# BMS028B_Monitor.net
KiCad netlist of a schematic drawn in Altium Designer
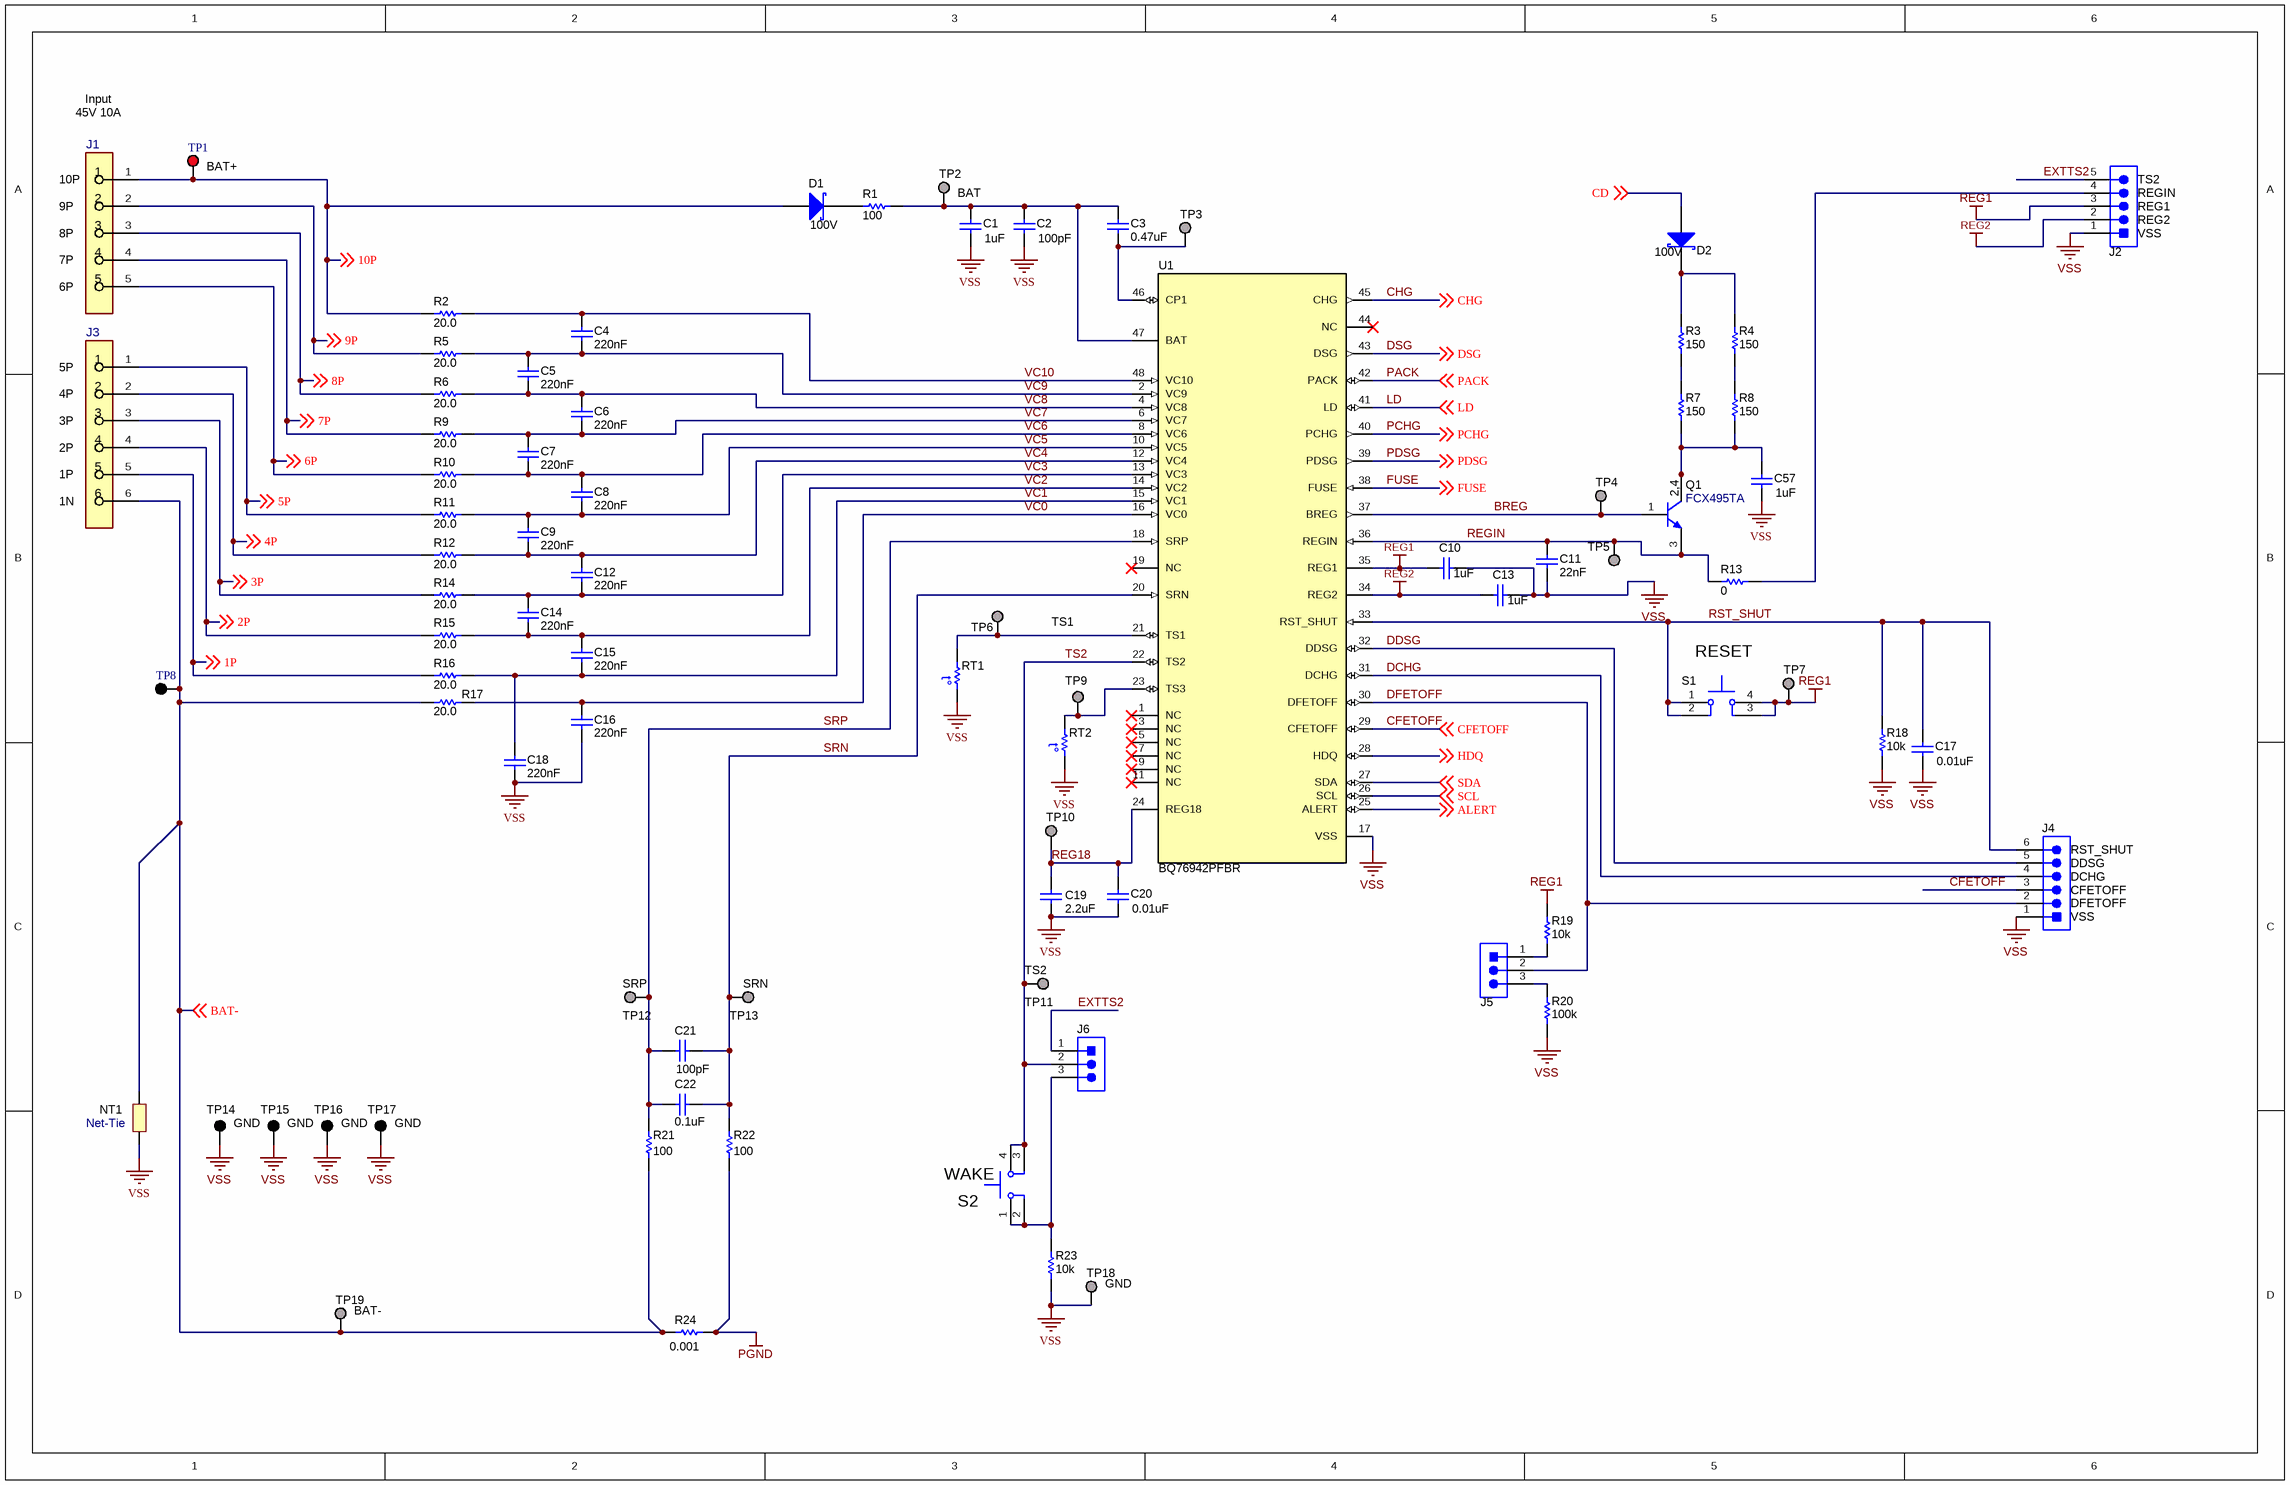
[diagram p0: BMS028B_Monitor.SchDoc]

(export (version "E")
  (design (tool "Eeschema 10.0.6"))
  (components
    (comp (ref "C1")
      (value "C3216X7R2A105K160AA")
      (footprint "1206_180")
      (description "CAP, CERM, 1 uF, 100 V, +/- 10%, X7R, 1206")
      (fields
        (field (name "MANUFACTURER") "TDK")
        (field (name "VALUEDISPLAYED") "1uF")
        (field (name "PUBLISHER") "Texas Instruments")
      )
      (libsource (lib "Altium Vault - TI") (part "Capacitor"))
    )
    (comp (ref "C2")
      (value "GCM1885C2A101JA16D")
      (footprint "0603")
      (description "CAP, CERM, 100 pF, 100 V, +/- 5%, C0G/NP0, AEC-Q200 Grade 1, 0603")
      (fields
        (field (name "MANUFACTURER") "MuRata")
        (field (name "VALUEDISPLAYED") "100pF")
        (field (name "PUBLISHER") "Texas Instruments")
      )
      (libsource (lib "Altium Vault - TI") (part "Capacitor"))
    )
    (comp (ref "C3")
      (value "GCM219R71E474KA55D")
      (footprint "0805_HV")
      (description "CAP, CERM, 0.47 uF, 25 V, +/- 10%, X7R, AEC-Q200 Grade 1, 0805")
      (fields
        (field (name "MANUFACTURER") "MuRata")
        (field (name "VALUEDISPLAYED") "0.47uF")
        (field (name "PUBLISHER") "Texas Instruments")
      )
      (libsource (lib "Altium Vault - TI") (part "Capacitor"))
    )
    (comp (ref "C4")
      (value "C1608X7R1H224K080AB")
      (footprint "0603S")
      (description "CAP, CERM, 0.22 uF, 50 V, +/- 10%, X7R, 0603")
      (fields
        (field (name "MANUFACTURER") "TDK")
        (field (name "CAP_F") "220nF")
        (field (name "PUBLISHER") "Texas Instruments")
      )
      (libsource (lib "Altium Vault - TI") (part "Capacitor"))
    )
    (comp (ref "C5")
      (value "C1608X7R1H224K080AB")
      (footprint "0603S")
      (description "CAP, CERM, 0.22 uF, 50 V, +/- 10%, X7R, 0603")
      (fields
        (field (name "MANUFACTURER") "TDK")
        (field (name "CAP_F") "220nF")
        (field (name "PUBLISHER") "Texas Instruments")
      )
      (libsource (lib "Altium Vault - TI") (part "Capacitor"))
    )
    (comp (ref "C6")
      (value "C1608X7R1H224K080AB")
      (footprint "0603S")
      (description "CAP, CERM, 0.22 uF, 50 V, +/- 10%, X7R, 0603")
      (fields
        (field (name "MANUFACTURER") "TDK")
        (field (name "CAP_F") "220nF")
        (field (name "PUBLISHER") "Texas Instruments")
      )
      (libsource (lib "Altium Vault - TI") (part "Capacitor"))
    )
    (comp (ref "C7")
      (value "C1608X7R1H224K080AB")
      (footprint "0603S")
      (description "CAP, CERM, 0.22 uF, 50 V, +/- 10%, X7R, 0603")
      (fields
        (field (name "MANUFACTURER") "TDK")
        (field (name "CAP_F") "220nF")
        (field (name "PUBLISHER") "Texas Instruments")
      )
      (libsource (lib "Altium Vault - TI") (part "Capacitor"))
    )
    (comp (ref "C8")
      (value "C1608X7R1H224K080AB")
      (footprint "0603S")
      (description "CAP, CERM, 0.22 uF, 50 V, +/- 10%, X7R, 0603")
      (fields
        (field (name "MANUFACTURER") "TDK")
        (field (name "CAP_F") "220nF")
        (field (name "PUBLISHER") "Texas Instruments")
      )
      (libsource (lib "Altium Vault - TI") (part "Capacitor"))
    )
    (comp (ref "C9")
      (value "C1608X7R1H224K080AB")
      (footprint "0603S")
      (description "CAP, CERM, 0.22 uF, 50 V, +/- 10%, X7R, 0603")
      (fields
        (field (name "MANUFACTURER") "TDK")
        (field (name "CAP_F") "220nF")
        (field (name "PUBLISHER") "Texas Instruments")
      )
      (libsource (lib "Altium Vault - TI") (part "Capacitor"))
    )
    (comp (ref "C10")
      (value "EMK212B7105KG-T")
      (footprint "0805_HV")
      (description "CAP, CERM, 1 uF, 16 V, +/- 10%, X7R, 0805")
      (fields
        (field (name "MANUFACTURER") "Taiyo Yuden")
        (field (name "VALUEDISPLAYED") "1uF")
        (field (name "PUBLISHER") "Texas Instruments")
      )
      (libsource (lib "Altium Vault - TI") (part "Capacitor"))
    )
    (comp (ref "C11")
      (value "C0603C223K4RACTU")
      (footprint "0603")
      (description "CAP, CERM, 0.022 uF, 16 V, +/- 10%, X7R, 0603")
      (fields
        (field (name "MANUFACTURER") "Kemet")
        (field (name "CAP_F") "22nF")
        (field (name "PUBLISHER") "Texas Instruments")
      )
      (libsource (lib "Altium Vault - TI") (part "Capacitor"))
    )
    (comp (ref "C12")
      (value "C1608X7R1H224K080AB")
      (footprint "0603S")
      (description "CAP, CERM, 0.22 uF, 50 V, +/- 10%, X7R, 0603")
      (fields
        (field (name "MANUFACTURER") "TDK")
        (field (name "CAP_F") "220nF")
        (field (name "PUBLISHER") "Texas Instruments")
      )
      (libsource (lib "Altium Vault - TI") (part "Capacitor"))
    )
    (comp (ref "C13")
      (value "EMK212B7105KG-T")
      (footprint "0805_HV")
      (description "CAP, CERM, 1 uF, 16 V, +/- 10%, X7R, 0805")
      (fields
        (field (name "MANUFACTURER") "Taiyo Yuden")
        (field (name "VALUEDISPLAYED") "1uF")
        (field (name "PUBLISHER") "Texas Instruments")
      )
      (libsource (lib "Altium Vault - TI") (part "Capacitor"))
    )
    (comp (ref "C14")
      (value "C1608X7R1H224K080AB")
      (footprint "0603S")
      (description "CAP, CERM, 0.22 uF, 50 V, +/- 10%, X7R, 0603")
      (fields
        (field (name "MANUFACTURER") "TDK")
        (field (name "CAP_F") "220nF")
        (field (name "PUBLISHER") "Texas Instruments")
      )
      (libsource (lib "Altium Vault - TI") (part "Capacitor"))
    )
    (comp (ref "C15")
      (value "C1608X7R1H224K080AB")
      (footprint "0603S")
      (description "CAP, CERM, 0.22 uF, 50 V, +/- 10%, X7R, 0603")
      (fields
        (field (name "MANUFACTURER") "TDK")
        (field (name "CAP_F") "220nF")
        (field (name "PUBLISHER") "Texas Instruments")
      )
      (libsource (lib "Altium Vault - TI") (part "Capacitor"))
    )
    (comp (ref "C16")
      (value "C1608X7R1H224K080AB")
      (footprint "0603S")
      (description "CAP, CERM, 0.22 uF, 50 V, +/- 10%, X7R, 0603")
      (fields
        (field (name "MANUFACTURER") "TDK")
        (field (name "CAP_F") "220nF")
        (field (name "PUBLISHER") "Texas Instruments")
      )
      (libsource (lib "Altium Vault - TI") (part "Capacitor"))
    )
    (comp (ref "C17")
      (value "885012206040")
      (footprint "0603")
      (description "CAP, CERM, 0.01 uF, 16 V, +/- 10%, X7R, 0603")
      (fields
        (field (name "MANUFACTURER") "Wurth Elektronik")
        (field (name "VALUEDISPLAYED") "0.01uF")
        (field (name "PUBLISHER") "Texas Instruments")
      )
      (libsource (lib "Altium Vault - TI") (part "Capacitor"))
    )
    (comp (ref "C18")
      (value "C1608X7R1H224K080AB")
      (footprint "0603S")
      (description "CAP, CERM, 0.22 uF, 50 V, +/- 10%, X7R, 0603")
      (fields
        (field (name "MANUFACTURER") "TDK")
        (field (name "CAP_F") "220nF")
        (field (name "PUBLISHER") "Texas Instruments")
      )
      (libsource (lib "Altium Vault - TI") (part "Capacitor"))
    )
    (comp (ref "C19")
      (value "EMK212B7225KG-T")
      (footprint "0805_HV")
      (description "CAP, CERM, 2.2 uF, 16 V, +/- 10%, X7R, 0805")
      (fields
        (field (name "MANUFACTURER") "Taiyo Yuden")
        (field (name "VALUEDISPLAYED") "2.2uF")
        (field (name "PUBLISHER") "Texas Instruments")
      )
      (libsource (lib "Altium Vault - TI") (part "Capacitor"))
    )
    (comp (ref "C20")
      (value "885012206040")
      (footprint "0603")
      (description "CAP, CERM, 0.01 uF, 16 V, +/- 10%, X7R, 0603")
      (fields
        (field (name "MANUFACTURER") "Wurth Elektronik")
        (field (name "VALUEDISPLAYED") "0.01uF")
        (field (name "PUBLISHER") "Texas Instruments")
      )
      (libsource (lib "Altium Vault - TI") (part "Capacitor"))
    )
    (comp (ref "C21")
      (value "C0603C101J5GACTU")
      (footprint "0603")
      (description "CAP, CERM, 100 pF, 50 V, +/- 5%, C0G/NP0, 0603")
      (fields
        (field (name "MANUFACTURER") "Kemet")
        (field (name "VALUEDISPLAYED") "100pF")
        (field (name "PUBLISHER") "Texas Instruments")
      )
      (libsource (lib "Altium Vault - TI") (part "Capacitor"))
    )
    (comp (ref "C22")
      (value "885012206095")
      (footprint "0603")
      (description "CAP, CERM, 0.1 uF, 50 V, +/- 10%, X7R, 0603")
      (fields
        (field (name "MANUFACTURER") "Wurth Elektronik")
        (field (name "VALUEDISPLAYED") "0.1uF")
        (field (name "PUBLISHER") "Texas Instruments")
      )
      (libsource (lib "Altium Vault - TI") (part "Capacitor"))
    )
    (comp (ref "C57")
      (value "C3216X7R2A105K160AA")
      (footprint "1206_180")
      (description "CAP, CERM, 1 uF, 100 V, +/- 10%, X7R, 1206")
      (fields
        (field (name "MANUFACTURER") "TDK")
        (field (name "VALUEDISPLAYED") "1uF")
        (field (name "PUBLISHER") "Texas Instruments")
      )
      (libsource (lib "Altium Vault - TI") (part "Capacitor"))
    )
    (comp (ref "D1")
      (value "100V")
      (footprint "SOD-123")
      (description "Diode, Schottky, 100 V, 0.15 A, SOD-123")
      (fields (field (name "MANUFACTURER") "Diodes Inc.") (field (name "PARTNUMBER") "BAT46W-7-F"))
      (libsource (lib "Altium Vault - TI") (part "DIODE_SCHOTTKY"))
    )
    (comp (ref "D2")
      (value "100V")
      (footprint "SOD-123")
      (description "Diode, Schottky, 100 V, 0.15 A, SOD-123")
      (fields (field (name "MANUFACTURER") "Diodes Inc.") (field (name "PARTNUMBER") "BAT46W-7-F"))
      (libsource (lib "Altium Vault - TI") (part "DIODE_SCHOTTKY"))
    )
    (comp (ref "J1")
      (value "OSTTE050161")
      (footprint "FP-OSTTE050161_HDR5-MFG")
      (description "TERM BLOCK 3.5MM VERT 5POS PCB")
      (fields (field (name "MANUFACTURER") "On Shore Technology"))
      (libsource (lib "Altium Vault - TI") (part "SYM-OSTTE050161"))
    )
    (comp (ref "J2")
      (value "PEC05SAAN")
      (footprint "Sullins_PxC05SAAN")
      (description "Header, 2.54mm, 5x1, Tin, TH")
      (fields
        (field (name "MANUFACTURER") "Sullins Connector Solutions")
        (field (name "PUBLISHER") "Texas Instruments")
      )
      (libsource (lib "Altium Vault - TI") (part "CMP-0054597-1"))
    )
    (comp (ref "J3")
      (value "OSTTE060161")
      (footprint "FP-OSTTE060161_HDR6-MFG")
      (description "TERM BLOCK 3.5MM VERT 6POS PCB")
      (fields (field (name "MANUFACTURER") "On Shore Technology"))
      (libsource (lib "Altium Vault - TI") (part "SYM-OSTTE060161"))
    )
    (comp (ref "J4")
      (value "PEC06SAAN")
      (footprint "Sullins_PEC06SAAN")
      (description "Header, 100mil, 6x1, Tin, TH")
      (fields
        (field (name "MANUFACTURER") "Sullins Connector Solutions")
        (field (name "PUBLISHER") "Texas Instruments")
      )
      (libsource (lib "Altium Vault - TI") (part "Header_6x1"))
    )
    (comp (ref "J5")
      (value "87898-0304")
      (footprint "Molex_87898-0304")
      (description "Header, 2.54mm, 3x1, Gold, SMT")
      (fields (field (name "MANUFACTURER") "Molex") (field (name "PUBLISHER") "Texas Instruments"))
      (libsource (lib "") (part "CMP-0075388-1_1"))
    )
    (comp (ref "J6")
      (value "87898-0304")
      (footprint "Molex_87898-0304")
      (description "Header, 2.54mm, 3x1, Gold, SMT")
      (fields (field (name "MANUFACTURER") "Molex") (field (name "PUBLISHER") "Texas Instruments"))
      (libsource (lib "Altium Vault - TI") (part "CMP-0075388-1"))
    )
    (comp (ref "NT1")
      (value "Net-Tie")
      (footprint "Net-Tie_10milWide_30milLong")
      (description "Single point connection between nets.")
      (libsource (lib "Altium Vault - TI") (part "Net-Tie"))
    )
    (comp (ref "Q1")
      (value "FCX495TA")
      (footprint "SOT-89-3")
      (description "Transistor, NPN, 150 V, 1 A, AEC-Q101, SOT-89")
      (fields (field (name "MANUFACTURER") "Diodes Inc.") (field (name "PUBLISHER") "Texas Instruments"))
      (libsource (lib "Altium Vault - TI") (part "BJT_NPN_C24B1E3"))
    )
    (comp (ref "R1")
      (value "Resistor")
      (footprint "0603")
      (description "RES, 100, 5%, 0.1 W, AEC-Q200 Grade 0, 0603")
      (fields
        (field (name "PARTNUMBER") "CRCW0603100RJNEA")
        (field (name "MANUFACTURER") "Vishay-Dale")
        (field (name "VALUEDISPLAYED") "100")
        (field (name "PUBLISHER") "Texas Instruments")
      )
      (libsource (lib "Altium Vault - TI") (part "Resistor"))
    )
    (comp (ref "R2")
      (value "CRCW120620R0FKEA")
      (footprint "1206")
      (description "RES, 20.0, 1%, 0.25 W, AEC-Q200 Grade 0, 1206")
      (fields (field (name "MANUFACTURER") "Vishay-Dale") (field (name "VALUEDISPLAYED") "20.0"))
      (libsource (lib "Altium Vault - TI") (part "Resistor"))
    )
    (comp (ref "R3")
      (value "CRCW2512150RJNEG")
      (footprint "2512")
      (description "RES, 150, 5%, 1 W, AEC-Q200 Grade 0, 2512")
      (fields (field (name "MANUFACTURER") "Vishay-Dale") (field (name "VALUEDISPLAYED") "150"))
      (libsource (lib "Altium Vault - TI") (part "Resistor"))
    )
    (comp (ref "R4")
      (value "CRCW2512150RJNEG")
      (footprint "2512")
      (description "RES, 150, 5%, 1 W, AEC-Q200 Grade 0, 2512")
      (fields (field (name "MANUFACTURER") "Vishay-Dale") (field (name "VALUEDISPLAYED") "150"))
      (libsource (lib "Altium Vault - TI") (part "Resistor"))
    )
    (comp (ref "R5")
      (value "CRCW120620R0FKEA")
      (footprint "1206")
      (description "RES, 20.0, 1%, 0.25 W, AEC-Q200 Grade 0, 1206")
      (fields (field (name "MANUFACTURER") "Vishay-Dale") (field (name "VALUEDISPLAYED") "20.0"))
      (libsource (lib "Altium Vault - TI") (part "Resistor"))
    )
    (comp (ref "R6")
      (value "CRCW120620R0FKEA")
      (footprint "1206")
      (description "RES, 20.0, 1%, 0.25 W, AEC-Q200 Grade 0, 1206")
      (fields (field (name "MANUFACTURER") "Vishay-Dale") (field (name "VALUEDISPLAYED") "20.0"))
      (libsource (lib "Altium Vault - TI") (part "CMP-0016781-3"))
    )
    (comp (ref "R7")
      (value "CRCW2512150RJNEG")
      (footprint "2512")
      (description "RES, 150, 5%, 1 W, AEC-Q200 Grade 0, 2512")
      (fields (field (name "MANUFACTURER") "Vishay-Dale") (field (name "VALUEDISPLAYED") "150"))
      (libsource (lib "Altium Vault - TI") (part "Resistor"))
    )
    (comp (ref "R8")
      (value "CRCW2512150RJNEG")
      (footprint "2512")
      (description "RES, 150, 5%, 1 W, AEC-Q200 Grade 0, 2512")
      (fields (field (name "MANUFACTURER") "Vishay-Dale") (field (name "VALUEDISPLAYED") "150"))
      (libsource (lib "Altium Vault - TI") (part "Resistor"))
    )
    (comp (ref "R9")
      (value "CRCW120620R0FKEA")
      (footprint "1206")
      (description "RES, 20.0, 1%, 0.25 W, AEC-Q200 Grade 0, 1206")
      (fields (field (name "MANUFACTURER") "Vishay-Dale") (field (name "VALUEDISPLAYED") "20.0"))
      (libsource (lib "Altium Vault - TI") (part "Resistor"))
    )
    (comp (ref "R10")
      (value "CRCW120620R0FKEA")
      (footprint "1206")
      (description "RES, 20.0, 1%, 0.25 W, AEC-Q200 Grade 0, 1206")
      (fields (field (name "MANUFACTURER") "Vishay-Dale") (field (name "VALUEDISPLAYED") "20.0"))
      (libsource (lib "Altium Vault - TI") (part "Resistor"))
    )
    (comp (ref "R11")
      (value "CRCW120620R0FKEA")
      (footprint "1206")
      (description "RES, 20.0, 1%, 0.25 W, AEC-Q200 Grade 0, 1206")
      (fields (field (name "MANUFACTURER") "Vishay-Dale") (field (name "VALUEDISPLAYED") "20.0"))
      (libsource (lib "Altium Vault - TI") (part "Resistor"))
    )
    (comp (ref "R12")
      (value "CRCW120620R0FKEA")
      (footprint "1206")
      (description "RES, 20.0, 1%, 0.25 W, AEC-Q200 Grade 0, 1206")
      (fields (field (name "MANUFACTURER") "Vishay-Dale") (field (name "VALUEDISPLAYED") "20.0"))
      (libsource (lib "Altium Vault - TI") (part "Resistor"))
    )
    (comp (ref "R13")
      (value "CRCW06030000Z0EA")
      (footprint "0603")
      (description "RES, 0, 5%, 0.1 W, AEC-Q200 Grade 0, 0603")
      (fields (field (name "MANUFACTURER") "Vishay-Dale") (field (name "VALUEDISPLAYED") "0"))
      (libsource (lib "Altium Vault - TI") (part "Resistor"))
    )
    (comp (ref "R14")
      (value "CRCW120620R0FKEA")
      (footprint "1206")
      (description "RES, 20.0, 1%, 0.25 W, AEC-Q200 Grade 0, 1206")
      (fields (field (name "MANUFACTURER") "Vishay-Dale") (field (name "VALUEDISPLAYED") "20.0"))
      (libsource (lib "Altium Vault - TI") (part "Resistor"))
    )
    (comp (ref "R15")
      (value "CRCW120620R0FKEA")
      (footprint "1206")
      (description "RES, 20.0, 1%, 0.25 W, AEC-Q200 Grade 0, 1206")
      (fields (field (name "MANUFACTURER") "Vishay-Dale") (field (name "VALUEDISPLAYED") "20.0"))
      (libsource (lib "Altium Vault - TI") (part "Resistor"))
    )
    (comp (ref "R16")
      (value "CRCW120620R0FKEA")
      (footprint "1206")
      (description "RES, 20.0, 1%, 0.25 W, AEC-Q200 Grade 0, 1206")
      (fields (field (name "MANUFACTURER") "Vishay-Dale") (field (name "VALUEDISPLAYED") "20.0"))
      (libsource (lib "Altium Vault - TI") (part "Resistor"))
    )
    (comp (ref "R17")
      (value "CRCW120620R0FKEA")
      (footprint "1206")
      (description "RES, 20.0, 1%, 0.25 W, AEC-Q200 Grade 0, 1206")
      (fields (field (name "MANUFACTURER") "Vishay-Dale") (field (name "VALUEDISPLAYED") "20.0"))
      (libsource (lib "Altium Vault - TI") (part "Resistor"))
    )
    (comp (ref "R18")
      (value "CRCW060310K0JNEA")
      (footprint "0603")
      (description "RES, 10 k, 5%, 0.1 W, AEC-Q200 Grade 0, 0603")
      (fields (field (name "MANUFACTURER") "Vishay-Dale") (field (name "VALUEDISPLAYED") "10k"))
      (libsource (lib "Altium Vault - TI") (part "Resistor"))
    )
    (comp (ref "R19")
      (value "CRCW060310K0JNEA")
      (footprint "0603")
      (description "RES, 10 k, 5%, 0.1 W, AEC-Q200 Grade 0, 0603")
      (fields (field (name "MANUFACTURER") "Vishay-Dale") (field (name "VALUEDISPLAYED") "10k"))
      (libsource (lib "Altium Vault - TI") (part "Resistor"))
    )
    (comp (ref "R20")
      (value "CRCW0603100KJNEA")
      (footprint "0603")
      (description "RES, 100 k, 5%, 0.1 W, AEC-Q200 Grade 0, 0603")
      (fields (field (name "MANUFACTURER") "Vishay-Dale") (field (name "VALUEDISPLAYED") "100k"))
      (libsource (lib "Altium Vault - TI") (part "Resistor"))
    )
    (comp (ref "R21")
      (value "Resistor")
      (footprint "0603")
      (description "RES, 100, 5%, 0.1 W, AEC-Q200 Grade 0, 0603")
      (fields
        (field (name "PARTNUMBER") "CRCW0603100RJNEA")
        (field (name "MANUFACTURER") "Vishay-Dale")
        (field (name "VALUEDISPLAYED") "100")
        (field (name "PUBLISHER") "Texas Instruments")
      )
      (libsource (lib "Altium Vault - TI") (part "Resistor"))
    )
    (comp (ref "R22")
      (value "Resistor")
      (footprint "0603")
      (description "RES, 100, 5%, 0.1 W, AEC-Q200 Grade 0, 0603")
      (fields
        (field (name "PARTNUMBER") "CRCW0603100RJNEA")
        (field (name "MANUFACTURER") "Vishay-Dale")
        (field (name "VALUEDISPLAYED") "100")
        (field (name "PUBLISHER") "Texas Instruments")
      )
      (libsource (lib "Altium Vault - TI") (part "Resistor"))
    )
    (comp (ref "R23")
      (value "CRCW060310K0JNEA")
      (footprint "0603")
      (description "RES, 10 k, 5%, 0.1 W, AEC-Q200 Grade 0, 0603")
      (fields (field (name "MANUFACTURER") "Vishay-Dale") (field (name "VALUEDISPLAYED") "10k"))
      (libsource (lib "Altium Vault - TI") (part "Resistor"))
    )
    (comp (ref "R24")
      (value "Resistor")
      (footprint "1210M")
      (description "RES, 0.001, 1%, 1 W, 1210")
      (fields
        (field (name "PARTNUMBER") "PMR25HZPFV1L00")
        (field (name "MANUFACTURER") "Rohm")
        (field (name "VALUEDISPLAYED") "0.001")
        (field (name "PUBLISHER") "Texas Instruments")
      )
      (libsource (lib "Altium Vault - TI") (part "Resistor"))
    )
    (comp (ref "RT1")
      (value "Thermistor")
      (footprint "THERMISTOR_103AT-2")
      (description "Thermistor NTC, 10.0k ohm, 1%, Disc, 5x8.4 mm")
      (fields
        (field (name "PARTNUMBER") "103AT-2")
        (field (name "MANUFACTURER") "SEMITEC Corporation")
        (field (name "PUBLISHER") "Texas Instruments")
      )
      (libsource (lib "Altium Vault - TI") (part "Thermistor"))
    )
    (comp (ref "RT2")
      (value "Thermistor")
      (footprint "THERMISTOR_103AT-2")
      (description "Thermistor NTC, 10.0k ohm, 1%, Disc, 5x8.4 mm")
      (fields
        (field (name "PARTNUMBER") "103AT-2")
        (field (name "MANUFACTURER") "SEMITEC Corporation")
        (field (name "PUBLISHER") "Texas Instruments")
      )
      (libsource (lib "Altium Vault - TI") (part "Thermistor"))
    )
    (comp (ref "S1")
      (value "SW_KST221JLFS")
      (footprint "SW_KST221JLFS")
      (description "Switch, Tactile, SPST-NO, SMT")
      (fields
        (field (name "PARTNUMBER") "KST221JLFS")
        (field (name "MANUFACTURER") "C&K Components")
        (field (name "SYMBOLCREATOR") "a0799628")
        (field (name "PUBLISHER") "Texas Instruments")
      )
      (libsource (lib "Altium Vault - TI") (part "SW_KST221JLFS"))
    )
    (comp (ref "S2")
      (value "SW_KST221JLFS")
      (footprint "SW_KST221JLFS")
      (description "Switch, Tactile, SPST-NO, SMT")
      (fields
        (field (name "PARTNUMBER") "KST221JLFS")
        (field (name "MANUFACTURER") "C&K Components")
        (field (name "SYMBOLCREATOR") "a0799628")
        (field (name "PUBLISHER") "Texas Instruments")
      )
      (libsource (lib "Altium Vault - TI") (part "SW_KST221JLFS"))
    )
    (comp (ref "TP1")
      (value "TESTPOINT")
      (footprint "Keystone5010")
      (description "Test Point, Multipurpose, Red, TH")
      (fields
        (field (name "MANUFACTURER") "Keystone")
        (field (name "PARTNUMBER") "5010")
        (field (name "PUBLISHER") "Texas Instruments")
      )
      (libsource (lib "Altium Vault - TI") (part "5010"))
    )
    (comp (ref "TP2")
      (value "TESTPOINT")
      (footprint "TP_VIA_060RND040")
      (description "TEST POINT.  No entry in BOM.")
      (libsource (lib "Altium Vault - TI") (part "TESTPOINT"))
    )
    (comp (ref "TP3")
      (value "TESTPOINT")
      (footprint "TP_VIA_060RND040")
      (description "TEST POINT.  No entry in BOM.")
      (libsource (lib "Altium Vault - TI") (part "CMP-0078143-2"))
    )
    (comp (ref "TP4")
      (value "TESTPOINT")
      (footprint "TP_VIA_060RND040")
      (description "TEST POINT.  No entry in BOM.")
      (libsource (lib "Altium Vault - TI") (part "CMP-0078143-2"))
    )
    (comp (ref "TP5")
      (value "TESTPOINT")
      (footprint "TP_VIA_060RND040")
      (description "TEST POINT.  No entry in BOM.")
      (libsource (lib "Altium Vault - TI") (part "CMP-0078143-2"))
    )
    (comp (ref "TP6")
      (value "TESTPOINT")
      (footprint "TP_VIA_060RND040")
      (description "TEST POINT.  No entry in BOM.")
      (libsource (lib "Altium Vault - TI") (part "CMP-0078143-2"))
    )
    (comp (ref "TP7")
      (value "TESTPOINT")
      (footprint "TP_VIA_060RND040")
      (description "TEST POINT.  No entry in BOM.")
      (libsource (lib "Altium Vault - TI") (part "CMP-0078143-2"))
    )
    (comp (ref "TP8")
      (value "TESTPOINT")
      (footprint "Keystone5011")
      (description "Test Point, Multipurpose, Black, TH")
      (fields
        (field (name "MANUFACTURER") "Keystone")
        (field (name "PARTNUMBER") "5011")
        (field (name "PUBLISHER") "Texas Instruments")
      )
      (libsource (lib "Altium Vault - TI") (part "5011"))
    )
    (comp (ref "TP9")
      (value "TESTPOINT")
      (footprint "TP_VIA_060RND040")
      (description "TEST POINT.  No entry in BOM.")
      (libsource (lib "Altium Vault - TI") (part "CMP-0078143-2"))
    )
    (comp (ref "TP10")
      (value "TESTPOINT")
      (footprint "TP_50MIL-25MILHOLE")
      (description "TEST POINT.  No entry in BOM.")
      (libsource (lib "Altium Vault - TI") (part "CMP-0078143-2"))
    )
    (comp (ref "TP11")
      (value "TESTPOINT")
      (footprint "TP_50MIL-25MILHOLE")
      (description "TEST POINT.  No entry in BOM.")
      (libsource (lib "Altium Vault - TI") (part "CMP-0078143-2"))
    )
    (comp (ref "TP12")
      (value "TESTPOINT")
      (footprint "TP_50MIL-25MILHOLE")
      (description "TEST POINT.  No entry in BOM.")
      (libsource (lib "Altium Vault - TI") (part "CMP-0078143-2"))
    )
    (comp (ref "TP13")
      (value "TESTPOINT")
      (footprint "TP_50MIL-25MILHOLE")
      (description "TEST POINT.  No entry in BOM.")
      (libsource (lib "Altium Vault - TI") (part "CMP-0078143-2"))
    )
    (comp (ref "TP14")
      (value "5006")
      (footprint "Keystone5006")
      (description "Test Point, Compact, Black, TH")
      (fields (field (name "MANUFACTURER") "Keystone") (field (name "PUBLISHER") "Texas Instruments"))
      (libsource (lib "Altium Vault - TI") (part "5006"))
    )
    (comp (ref "TP15")
      (value "5006")
      (footprint "Keystone5006")
      (description "Test Point, Compact, Black, TH")
      (fields (field (name "MANUFACTURER") "Keystone") (field (name "PUBLISHER") "Texas Instruments"))
      (libsource (lib "Altium Vault - TI") (part "5006"))
    )
    (comp (ref "TP16")
      (value "5006")
      (footprint "Keystone5006")
      (description "Test Point, Compact, Black, TH")
      (fields (field (name "MANUFACTURER") "Keystone") (field (name "PUBLISHER") "Texas Instruments"))
      (libsource (lib "Altium Vault - TI") (part "5006"))
    )
    (comp (ref "TP17")
      (value "5006")
      (footprint "Keystone5006")
      (description "Test Point, Compact, Black, TH")
      (fields (field (name "MANUFACTURER") "Keystone") (field (name "PUBLISHER") "Texas Instruments"))
      (libsource (lib "Altium Vault - TI") (part "5006"))
    )
    (comp (ref "TP18")
      (value "TESTPOINT")
      (footprint "TP_VIA_060RND040")
      (description "TEST POINT.  No entry in BOM.")
      (libsource (lib "Altium Vault - TI") (part "TESTPOINT"))
    )
    (comp (ref "TP19")
      (value "TESTPOINT")
      (footprint "TP_VIA_060RND040")
      (description "TEST POINT.  No entry in BOM.")
      (libsource (lib "Altium Vault - TI") (part "TESTPOINT"))
    )
    (comp (ref "U1")
      (value "BQ76942PFBR")
      (footprint "PFB0048A_N")
      (description "Multicell Battery Monitor and Protection Family, PFB0048A (TQFP-48)")
      (fields
        (field (name "ALTERNATE PARTNUMBER") "BQ76942PFBT")
        (field (name "MANUFACTURER") "Texas Instruments")
        (field (name "PARTNUMBER") "BQ76942PFBR")
      )
      (libsource (lib "Altium Vault - TI") (part "bq76942"))
    )
  )
  (nets
    (net (code "1") (name "/BREG") (class "Default")
      (node (ref "Q1") (pin "1") (pinfunction "B_1") (pintype "passive"))
      (node (ref "TP4") (pin "1") (pintype "passive"))
      (node (ref "U1") (pin "37") (pinfunction "BREG_37") (pintype "output"))
    )
    (net (code "2") (name "/DCHG") (class "Default")
      (node (ref "J4") (pin "4") (pinfunction "4_4") (pintype "passive"))
      (node (ref "U1") (pin "31") (pinfunction "DCHG_31") (pintype "bidirectional"))
    )
    (net (code "3") (name "/DDSG") (class "Default")
      (node (ref "J4") (pin "5") (pinfunction "5_5") (pintype "passive"))
      (node (ref "U1") (pin "32") (pinfunction "DDSG_32") (pintype "bidirectional"))
    )
    (net (code "4") (name "/DFETOFF") (class "Default")
      (node (ref "J4") (pin "2") (pinfunction "2_2") (pintype "passive"))
      (node (ref "J5") (pin "2") (pinfunction "2_2") (pintype "passive"))
      (node (ref "U1") (pin "30") (pinfunction "DFETOFF_30") (pintype "bidirectional"))
    )
    (net (code "5") (name "/EXTTS2") (class "Default")
      (node (ref "J2") (pin "5") (pinfunction "5_5") (pintype "passive"))
      (node (ref "J6") (pin "1") (pinfunction "1_1") (pintype "passive"))
    )
    (net (code "6") (name "/REG18") (class "Default")
      (node (ref "C19") (pin "2") (pinfunction "2_2") (pintype "passive"))
      (node (ref "C20") (pin "1") (pinfunction "1_1") (pintype "passive"))
      (node (ref "TP10") (pin "1") (pintype "passive"))
      (node (ref "U1") (pin "24") (pinfunction "REG18_24") (pintype "power_in"))
    )
    (net (code "7") (name "/REGIN") (class "Default")
      (node (ref "C11") (pin "2") (pinfunction "2_2") (pintype "passive"))
      (node (ref "Q1") (pin "3") (pinfunction "E_3") (pintype "passive"))
      (node (ref "R13") (pin "1") (pinfunction "1_1") (pintype "passive"))
      (node (ref "TP5") (pin "1") (pintype "passive"))
      (node (ref "U1") (pin "36") (pinfunction "REGIN_36") (pintype "input"))
    )
    (net (code "8") (name "/RST_SHUT") (class "Default")
      (node (ref "C17") (pin "1") (pinfunction "1_1") (pintype "passive"))
      (node (ref "J4") (pin "6") (pinfunction "6_6") (pintype "passive"))
      (node (ref "R18") (pin "1") (pinfunction "1_1") (pintype "passive"))
      (node (ref "S1") (pin "1") (pinfunction "1_1") (pintype "passive"))
      (node (ref "S1") (pin "2") (pinfunction "2_2") (pintype "passive"))
      (node (ref "U1") (pin "33") (pinfunction "RST_SHUT_33") (pintype "input"))
    )
    (net (code "9") (name "/SRN") (class "Default")
      (node (ref "C21") (pin "1") (pinfunction "1_1") (pintype "passive"))
      (node (ref "C22") (pin "2") (pinfunction "2_2") (pintype "passive"))
      (node (ref "R22") (pin "2") (pinfunction "2_2") (pintype "passive"))
      (node (ref "TP13") (pin "1") (pintype "passive"))
      (node (ref "U1") (pin "20") (pinfunction "SRN_20") (pintype "input"))
    )
    (net (code "10") (name "/SRP") (class "Default")
      (node (ref "C21") (pin "2") (pinfunction "2_2") (pintype "passive"))
      (node (ref "C22") (pin "1") (pinfunction "1_1") (pintype "passive"))
      (node (ref "R21") (pin "2") (pinfunction "2_2") (pintype "passive"))
      (node (ref "TP12") (pin "1") (pintype "passive"))
      (node (ref "U1") (pin "18") (pinfunction "SRP_18") (pintype "input"))
    )
    (net (code "11") (name "/TS2") (class "Default")
      (node (ref "J6") (pin "2") (pinfunction "2_2") (pintype "passive"))
      (node (ref "S2") (pin "3") (pinfunction "3_3") (pintype "passive"))
      (node (ref "S2") (pin "4") (pinfunction "4_4") (pintype "passive"))
      (node (ref "TP11") (pin "1") (pintype "passive"))
      (node (ref "U1") (pin "22") (pinfunction "TS2_22") (pintype "bidirectional"))
    )
    (net (code "12") (name "/VC0") (class "Default")
      (node (ref "C16") (pin "1") (pinfunction "1_1") (pintype "passive"))
      (node (ref "R17") (pin "2") (pinfunction "2_2") (pintype "passive"))
      (node (ref "U1") (pin "16") (pinfunction "VC0_16") (pintype "input"))
    )
    (net (code "13") (name "/VC1") (class "Default")
      (node (ref "C15") (pin "2") (pinfunction "2_2") (pintype "passive"))
      (node (ref "C18") (pin "1") (pinfunction "1_1") (pintype "passive"))
      (node (ref "R16") (pin "2") (pinfunction "2_2") (pintype "passive"))
      (node (ref "U1") (pin "15") (pinfunction "VC1_15") (pintype "input"))
    )
    (net (code "14") (name "/VC2") (class "Default")
      (node (ref "C14") (pin "2") (pinfunction "2_2") (pintype "passive"))
      (node (ref "C15") (pin "1") (pinfunction "1_1") (pintype "passive"))
      (node (ref "R15") (pin "2") (pinfunction "2_2") (pintype "passive"))
      (node (ref "U1") (pin "14") (pinfunction "VC2_14") (pintype "input"))
    )
    (net (code "15") (name "/VC3") (class "Default")
      (node (ref "C12") (pin "2") (pinfunction "2_2") (pintype "passive"))
      (node (ref "C14") (pin "1") (pinfunction "1_1") (pintype "passive"))
      (node (ref "R14") (pin "2") (pinfunction "2_2") (pintype "passive"))
      (node (ref "U1") (pin "13") (pinfunction "VC3_13") (pintype "input"))
    )
    (net (code "16") (name "/VC4") (class "Default")
      (node (ref "C12") (pin "1") (pinfunction "1_1") (pintype "passive"))
      (node (ref "C9") (pin "2") (pinfunction "2_2") (pintype "passive"))
      (node (ref "R12") (pin "2") (pinfunction "2_2") (pintype "passive"))
      (node (ref "U1") (pin "12") (pinfunction "VC4_12") (pintype "input"))
    )
    (net (code "17") (name "/VC5") (class "Default")
      (node (ref "C8") (pin "2") (pinfunction "2_2") (pintype "passive"))
      (node (ref "C9") (pin "1") (pinfunction "1_1") (pintype "passive"))
      (node (ref "R11") (pin "2") (pinfunction "2_2") (pintype "passive"))
      (node (ref "U1") (pin "10") (pinfunction "VC5_10") (pintype "input"))
    )
    (net (code "18") (name "/VC6") (class "Default")
      (node (ref "C7") (pin "2") (pinfunction "2_2") (pintype "passive"))
      (node (ref "C8") (pin "1") (pinfunction "1_1") (pintype "passive"))
      (node (ref "R10") (pin "2") (pinfunction "2_2") (pintype "passive"))
      (node (ref "U1") (pin "8") (pinfunction "VC6_8") (pintype "input"))
    )
    (net (code "19") (name "/VC7") (class "Default")
      (node (ref "C6") (pin "2") (pinfunction "2_2") (pintype "passive"))
      (node (ref "C7") (pin "1") (pinfunction "1_1") (pintype "passive"))
      (node (ref "R9") (pin "2") (pinfunction "2_2") (pintype "passive"))
      (node (ref "U1") (pin "6") (pinfunction "VC7_6") (pintype "input"))
    )
    (net (code "20") (name "/VC8") (class "Default")
      (node (ref "C5") (pin "2") (pinfunction "2_2") (pintype "passive"))
      (node (ref "C6") (pin "1") (pinfunction "1_1") (pintype "passive"))
      (node (ref "R6") (pin "2") (pinfunction "2_2") (pintype "passive"))
      (node (ref "U1") (pin "4") (pinfunction "VC8_4") (pintype "input"))
    )
    (net (code "21") (name "/VC9") (class "Default")
      (node (ref "C4") (pin "2") (pinfunction "2_2") (pintype "passive"))
      (node (ref "C5") (pin "1") (pinfunction "1_1") (pintype "passive"))
      (node (ref "R5") (pin "2") (pinfunction "2_2") (pintype "passive"))
      (node (ref "U1") (pin "2") (pinfunction "VC9_2") (pintype "input"))
    )
    (net (code "22") (name "/VC10") (class "Default")
      (node (ref "C4") (pin "1") (pinfunction "1_1") (pintype "passive"))
      (node (ref "R2") (pin "2") (pinfunction "2_2") (pintype "passive"))
      (node (ref "U1") (pin "48") (pinfunction "VC10_48") (pintype "input"))
    )
    (net (code "23") (name "1P") (class "Default")
      (node (ref "J3") (pin "5") (pinfunction "5_5") (pintype "passive"))
      (node (ref "R16") (pin "1") (pinfunction "1_1") (pintype "passive"))
    )
    (net (code "24") (name "2P") (class "Default")
      (node (ref "J3") (pin "4") (pinfunction "4_4") (pintype "passive"))
      (node (ref "R15") (pin "1") (pinfunction "1_1") (pintype "passive"))
    )
    (net (code "25") (name "3P") (class "Default")
      (node (ref "J3") (pin "3") (pinfunction "3_3") (pintype "passive"))
      (node (ref "R14") (pin "1") (pinfunction "1_1") (pintype "passive"))
    )
    (net (code "26") (name "4P") (class "Default")
      (node (ref "J3") (pin "2") (pinfunction "2_2") (pintype "passive"))
      (node (ref "R12") (pin "1") (pinfunction "1_1") (pintype "passive"))
    )
    (net (code "27") (name "5P") (class "Default")
      (node (ref "J3") (pin "1") (pinfunction "1_1") (pintype "passive"))
      (node (ref "R11") (pin "1") (pinfunction "1_1") (pintype "passive"))
    )
    (net (code "28") (name "6P") (class "Default")
      (node (ref "J1") (pin "5") (pinfunction "5_5") (pintype "passive"))
      (node (ref "R10") (pin "1") (pinfunction "1_1") (pintype "passive"))
    )
    (net (code "29") (name "7P") (class "Default")
      (node (ref "J1") (pin "4") (pinfunction "4_4") (pintype "passive"))
      (node (ref "R9") (pin "1") (pinfunction "1_1") (pintype "passive"))
    )
    (net (code "30") (name "8P") (class "Default")
      (node (ref "J1") (pin "3") (pinfunction "3_3") (pintype "passive"))
      (node (ref "R6") (pin "1") (pinfunction "1_1") (pintype "passive"))
    )
    (net (code "31") (name "9P") (class "Default")
      (node (ref "J1") (pin "2") (pinfunction "2_2") (pintype "passive"))
      (node (ref "R5") (pin "1") (pinfunction "1_1") (pintype "passive"))
    )
    (net (code "32") (name "10P") (class "Default")
      (node (ref "D1") (pin "2") (pinfunction "A_2") (pintype "passive"))
      (node (ref "J1") (pin "1") (pinfunction "1_1") (pintype "passive"))
      (node (ref "R2") (pin "1") (pinfunction "1_1") (pintype "passive"))
      (node (ref "TP1") (pin "1") (pintype "passive"))
    )
    (net (code "33") (name "ALERT") (class "Default")
      (node (ref "U1") (pin "25") (pinfunction "ALERT_25") (pintype "bidirectional"))
    )
    (net (code "34") (name "BAT-") (class "Default")
      (node (ref "J3") (pin "6") (pinfunction "6_6") (pintype "passive"))
      (node (ref "NT1") (pin "2") (pinfunction "2_2") (pintype "passive"))
      (node (ref "R17") (pin "1") (pinfunction "1_1") (pintype "passive"))
      (node (ref "R21") (pin "1") (pinfunction "1_1") (pintype "passive"))
      (node (ref "R24") (pin "2") (pinfunction "2_2") (pintype "passive"))
      (node (ref "TP19") (pin "1") (pintype "passive"))
      (node (ref "TP8") (pin "1") (pintype "passive"))
    )
    (net (code "35") (name "CD") (class "Default")
      (node (ref "D2") (pin "2") (pinfunction "A_2") (pintype "passive"))
    )
    (net (code "36") (name "CFETOFF") (class "Default")
      (node (ref "J4") (pin "3") (pinfunction "3_3") (pintype "passive"))
      (node (ref "U1") (pin "29") (pinfunction "CFETOFF_29") (pintype "bidirectional"))
    )
    (net (code "37") (name "CHG") (class "Default")
      (node (ref "U1") (pin "45") (pinfunction "CHG_45") (pintype "output"))
    )
    (net (code "38") (name "DSG") (class "Default")
      (node (ref "U1") (pin "43") (pinfunction "DSG_43") (pintype "output"))
    )
    (net (code "39") (name "FUSE") (class "Default")
      (node (ref "U1") (pin "38") (pinfunction "FUSE_38") (pintype "input"))
    )
    (net (code "40") (name "HDQ") (class "Default")
      (node (ref "U1") (pin "28") (pinfunction "HDQ_28") (pintype "bidirectional"))
    )
    (net (code "41") (name "LD") (class "Default")
      (node (ref "U1") (pin "41") (pinfunction "LD_41") (pintype "bidirectional"))
    )
    (net (code "42") (name "Net-(C57-Pad1)") (class "Default")
      (node (ref "C57") (pin "1") (pinfunction "1_1") (pintype "passive"))
      (node (ref "Q1") (pin "2") (pinfunction "C_2") (pintype "passive"))
      (node (ref "Q1") (pin "4") (pinfunction "C_4") (pintype "passive"))
      (node (ref "R7") (pin "1") (pinfunction "1_1") (pintype "passive"))
      (node (ref "R8") (pin "1") (pinfunction "1_1") (pintype "passive"))
    )
    (net (code "43") (name "Net-(D1-K)") (class "Default")
      (node (ref "D1") (pin "1") (pinfunction "K_1") (pintype "passive"))
      (node (ref "R1") (pin "2") (pinfunction "2_2") (pintype "passive"))
    )
    (net (code "44") (name "Net-(D2-K)") (class "Default")
      (node (ref "D2") (pin "1") (pinfunction "K_1") (pintype "passive"))
      (node (ref "R3") (pin "2") (pinfunction "2_2") (pintype "passive"))
      (node (ref "R4") (pin "2") (pinfunction "2_2") (pintype "passive"))
    )
    (net (code "45") (name "Net-(J2-Pad4)") (class "Default")
      (node (ref "J2") (pin "4") (pinfunction "4_4") (pintype "passive"))
      (node (ref "R13") (pin "2") (pinfunction "2_2") (pintype "passive"))
    )
    (net (code "46") (name "Net-(J5-Pad1)") (class "Default")
      (node (ref "J5") (pin "1") (pinfunction "1_1") (pintype "passive"))
      (node (ref "R19") (pin "2") (pinfunction "2_2") (pintype "passive"))
    )
    (net (code "47") (name "Net-(J5-Pad3)") (class "Default")
      (node (ref "J5") (pin "3") (pinfunction "3_3") (pintype "passive"))
      (node (ref "R20") (pin "2") (pinfunction "2_2") (pintype "passive"))
    )
    (net (code "48") (name "Net-(J6-Pad3)") (class "Default")
      (node (ref "J6") (pin "3") (pinfunction "3_3") (pintype "passive"))
      (node (ref "R23") (pin "2") (pinfunction "2_2") (pintype "passive"))
      (node (ref "S2") (pin "1") (pinfunction "1_1") (pintype "passive"))
      (node (ref "S2") (pin "2") (pinfunction "2_2") (pintype "passive"))
    )
    (net (code "49") (name "Net-(R3-Pad1)") (class "Default")
      (node (ref "R3") (pin "1") (pinfunction "1_1") (pintype "passive"))
      (node (ref "R7") (pin "2") (pinfunction "2_2") (pintype "passive"))
    )
    (net (code "50") (name "Net-(R4-Pad1)") (class "Default")
      (node (ref "R4") (pin "1") (pinfunction "1_1") (pintype "passive"))
      (node (ref "R8") (pin "2") (pinfunction "2_2") (pintype "passive"))
    )
    (net (code "51") (name "Net-(U1-BAT)") (class "Default")
      (node (ref "C1") (pin "1") (pinfunction "1_1") (pintype "passive"))
      (node (ref "C2") (pin "1") (pinfunction "1_1") (pintype "passive"))
      (node (ref "C3") (pin "1") (pinfunction "1_1") (pintype "passive"))
      (node (ref "R1") (pin "1") (pinfunction "1_1") (pintype "passive"))
      (node (ref "TP2") (pin "1") (pintype "passive"))
      (node (ref "U1") (pin "47") (pinfunction "BAT_47") (pintype "power_in"))
    )
    (net (code "52") (name "Net-(U1-CP1)") (class "Default")
      (node (ref "C3") (pin "2") (pinfunction "2_2") (pintype "passive"))
      (node (ref "TP3") (pin "1") (pintype "passive"))
      (node (ref "U1") (pin "46") (pinfunction "CP1_46") (pintype "bidirectional"))
    )
    (net (code "53") (name "Net-(U1-TS1)") (class "Default")
      (node (ref "RT1") (pin "1") (pinfunction "1_1") (pintype "passive"))
      (node (ref "TP6") (pin "1") (pintype "passive"))
      (node (ref "U1") (pin "21") (pinfunction "TS1_21") (pintype "bidirectional"))
    )
    (net (code "54") (name "Net-(U1-TS3)") (class "Default")
      (node (ref "RT2") (pin "1") (pinfunction "1_1") (pintype "passive"))
      (node (ref "TP9") (pin "1") (pintype "passive"))
      (node (ref "U1") (pin "23") (pinfunction "TS3_23") (pintype "bidirectional"))
    )
    (net (code "55") (name "PACK") (class "Default")
      (node (ref "U1") (pin "42") (pinfunction "PACK_42") (pintype "bidirectional"))
    )
    (net (code "56") (name "PCHG") (class "Default")
      (node (ref "U1") (pin "40") (pinfunction "PCHG_40") (pintype "output"))
    )
    (net (code "57") (name "PDSG") (class "Default")
      (node (ref "U1") (pin "39") (pinfunction "PDSG_39") (pintype "output"))
    )
    (net (code "58") (name "PGND") (class "Default")
      (node (ref "R22") (pin "1") (pinfunction "1_1") (pintype "passive"))
      (node (ref "R24") (pin "1") (pinfunction "1_1") (pintype "passive"))
    )
    (net (code "59") (name "REG1") (class "Default")
      (node (ref "C10") (pin "2") (pinfunction "2_2") (pintype "passive"))
      (node (ref "J2") (pin "3") (pinfunction "3_3") (pintype "passive"))
      (node (ref "R19") (pin "1") (pinfunction "1_1") (pintype "passive"))
      (node (ref "S1") (pin "3") (pinfunction "3_3") (pintype "passive"))
      (node (ref "S1") (pin "4") (pinfunction "4_4") (pintype "passive"))
      (node (ref "TP7") (pin "1") (pintype "passive"))
      (node (ref "U1") (pin "35") (pinfunction "REG1_35") (pintype "power_in"))
    )
    (net (code "60") (name "REG2") (class "Default")
      (node (ref "C13") (pin "2") (pinfunction "2_2") (pintype "passive"))
      (node (ref "J2") (pin "2") (pinfunction "2_2") (pintype "passive"))
      (node (ref "U1") (pin "34") (pinfunction "REG2_34") (pintype "power_in"))
    )
    (net (code "61") (name "SCL") (class "Default")
      (node (ref "U1") (pin "26") (pinfunction "SCL_26") (pintype "bidirectional"))
    )
    (net (code "62") (name "SDA") (class "Default")
      (node (ref "U1") (pin "27") (pinfunction "SDA_27") (pintype "bidirectional"))
    )
    (net (code "63") (name "VSS") (class "Default")
      (node (ref "C1") (pin "2") (pinfunction "2_2") (pintype "passive"))
      (node (ref "C10") (pin "1") (pinfunction "1_1") (pintype "passive"))
      (node (ref "C11") (pin "1") (pinfunction "1_1") (pintype "passive"))
      (node (ref "C13") (pin "1") (pinfunction "1_1") (pintype "passive"))
      (node (ref "C16") (pin "2") (pinfunction "2_2") (pintype "passive"))
      (node (ref "C17") (pin "2") (pinfunction "2_2") (pintype "passive"))
      (node (ref "C18") (pin "2") (pinfunction "2_2") (pintype "passive"))
      (node (ref "C19") (pin "1") (pinfunction "1_1") (pintype "passive"))
      (node (ref "C2") (pin "2") (pinfunction "2_2") (pintype "passive"))
      (node (ref "C20") (pin "2") (pinfunction "2_2") (pintype "passive"))
      (node (ref "C57") (pin "2") (pinfunction "2_2") (pintype "passive"))
      (node (ref "J2") (pin "1") (pinfunction "1_1") (pintype "passive"))
      (node (ref "J4") (pin "1") (pinfunction "1_1") (pintype "passive"))
      (node (ref "NT1") (pin "1") (pinfunction "1_1") (pintype "passive"))
      (node (ref "R18") (pin "2") (pinfunction "2_2") (pintype "passive"))
      (node (ref "R20") (pin "1") (pinfunction "1_1") (pintype "passive"))
      (node (ref "R23") (pin "1") (pinfunction "1_1") (pintype "passive"))
      (node (ref "RT1") (pin "2") (pinfunction "2_2") (pintype "passive"))
      (node (ref "RT2") (pin "2") (pinfunction "2_2") (pintype "passive"))
      (node (ref "TP14") (pin "1") (pintype "passive"))
      (node (ref "TP15") (pin "1") (pintype "passive"))
      (node (ref "TP16") (pin "1") (pintype "passive"))
      (node (ref "TP17") (pin "1") (pintype "passive"))
      (node (ref "TP18") (pin "1") (pintype "passive"))
      (node (ref "U1") (pin "17") (pinfunction "VSS_17") (pintype "power_in"))
    )
    (net (code "64") (name "unconnected-(U1-NC-Pad1)") (class "Default")
      (node (ref "U1") (pin "1") (pinfunction "NC_1") (pintype "passive+no_connect"))
    )
    (net (code "65") (name "unconnected-(U1-NC-Pad3)") (class "Default")
      (node (ref "U1") (pin "3") (pinfunction "NC_3") (pintype "passive+no_connect"))
    )
    (net (code "66") (name "unconnected-(U1-NC-Pad5)") (class "Default")
      (node (ref "U1") (pin "5") (pinfunction "NC_5") (pintype "passive+no_connect"))
    )
    (net (code "67") (name "unconnected-(U1-NC-Pad7)") (class "Default")
      (node (ref "U1") (pin "7") (pinfunction "NC_7") (pintype "passive+no_connect"))
    )
    (net (code "68") (name "unconnected-(U1-NC-Pad9)") (class "Default")
      (node (ref "U1") (pin "9") (pinfunction "NC_9") (pintype "passive+no_connect"))
    )
    (net (code "69") (name "unconnected-(U1-NC-Pad11)") (class "Default")
      (node (ref "U1") (pin "11") (pinfunction "NC_11") (pintype "passive+no_connect"))
    )
    (net (code "70") (name "unconnected-(U1-NC-Pad19)") (class "Default")
      (node (ref "U1") (pin "19") (pinfunction "NC_19") (pintype "passive+no_connect"))
    )
    (net (code "71") (name "unconnected-(U1-NC-Pad44)") (class "Default")
      (node (ref "U1") (pin "44") (pinfunction "NC_44") (pintype "passive+no_connect"))
    )
  )
)
